# PERIPHERALS.net
KiCad netlist of a schematic drawn in Altium Designer
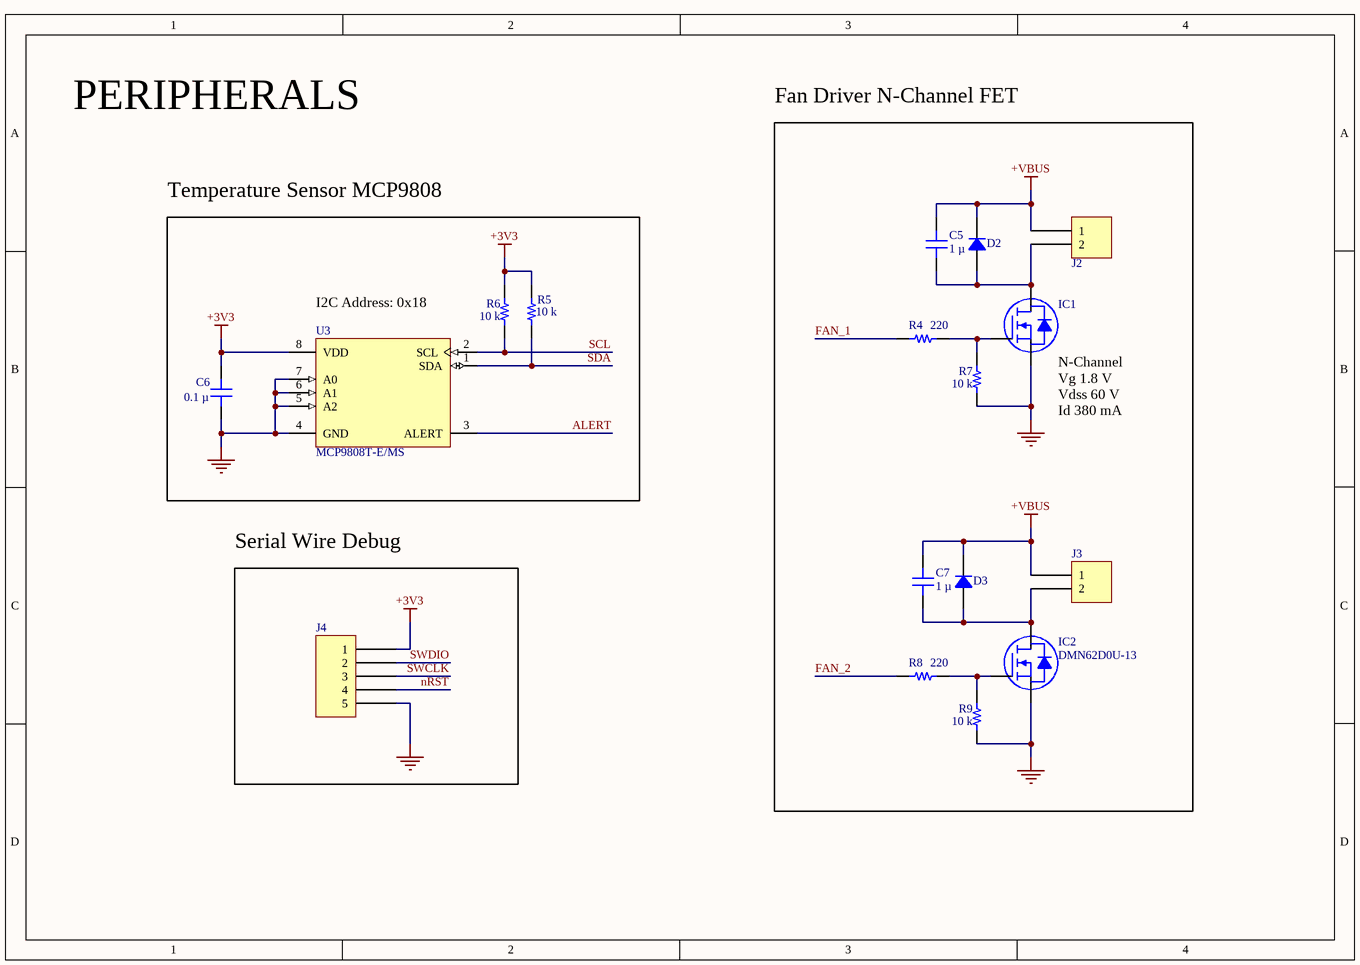
[diagram p0: PERIPHERALS.SchDoc]

(export (version "E")
  (design (tool "Eeschema 10.0.6"))
  (components
    (comp (ref "C5")
      (value "1 µ")
      (footprint "CAP 0603_1608")
      (description "CAP CER 1UF 16V X7R 0603")
      (fields (field (name "PART NUMBER") "C0603C105K4RACAUTO") (field (name "MANUFACTURER") "KEMET"))
      (libsource (lib "Celestial Altium Library - altium_library") (part "Capacitor"))
    )
    (comp (ref "C6")
      (value "0.1 µ")
      (footprint "CAP 0603_1608")
      (description "CAP CER 0.1UF 50V X7R 0603")
      (fields (field (name "PART NUMBER") "C0603C104K5RAC7411") (field (name "MANUFACTURER") "KEMET"))
      (libsource (lib "Celestial Altium Library - altium_library") (part "Capacitor"))
    )
    (comp (ref "C7")
      (value "1 µ")
      (footprint "CAP 0603_1608")
      (description "CAP CER 1UF 16V X7R 0603")
      (fields (field (name "PART NUMBER") "C0603C105K4RACAUTO") (field (name "MANUFACTURER") "KEMET"))
      (libsource (lib "Celestial Altium Library - altium_library") (part "Capacitor"))
    )
    (comp (ref "D2")
      (value "US1DWF-7")
      (footprint "SOD123F")
      (description "DIODE GEN PURP 200V 1A SOD123F")
      (fields (field (name "MANUFACTURER") "Diodes Incorporated"))
      (libsource (lib "Celestial Altium Library - altium_library") (part "Diode"))
    )
    (comp (ref "D3")
      (value "US1DWF-7")
      (footprint "SOD123F")
      (description "DIODE GEN PURP 200V 1A SOD123F")
      (fields (field (name "MANUFACTURER") "Diodes Incorporated"))
      (libsource (lib "Celestial Altium Library - altium_library") (part "Diode"))
    )
    (comp (ref "IC1")
      (value "DMN62D0U-13")
      (footprint "DIODES SOT-23-3")
      (description "MOSFET N-CH 60V 380MA SOT23")
      (fields (field (name "MANUFACTURER") "Diodes Incorporated"))
      (libsource (lib "Celestial Altium Library - altium_library") (part "DIODES INC MOSFET N-CH SOT-23-3"))
    )
    (comp (ref "IC2")
      (value "DMN62D0U-13")
      (footprint "DIODES SOT-23-3")
      (description "MOSFET N-CH 60V 380MA SOT23")
      (fields (field (name "MANUFACTURER") "Diodes Incorporated"))
      (libsource (lib "Celestial Altium Library - altium_library") (part "DIODES INC MOSFET N-CH SOT-23-3"))
    )
    (comp (ref "J2")
      (value "S2B-PH-SM4-TB(LF)(SN)")
      (footprint "JST S2B-PH-SM4-TB")
      (description "CONN HEADER SMD R/A 2POS 2MM")
      (fields (field (name "MANUFACTURER") "JST Sales America Inc."))
      (libsource (lib "Celestial Altium Library - altium_library") (part "2 Pin"))
    )
    (comp (ref "J3")
      (value "S2B-PH-SM4-TB(LF)(SN)")
      (footprint "JST S2B-PH-SM4-TB")
      (description "CONN HEADER SMD R/A 2POS 2MM")
      (fields (field (name "MANUFACTURER") "JST Sales America Inc."))
      (libsource (lib "Celestial Altium Library - altium_library") (part "2 Pin"))
    )
    (comp (ref "J4")
      (value "NPPN051BFCN-RC")
      (footprint "SULLINS NPPN051BFCN")
      (description "CONN HDR 5POS 0.079 GOLD PCB")
      (fields (field (name "MANUFACTURER") "Sullins Connector Solutions"))
      (libsource (lib "Celestial Altium Library - altium_library") (part "5 Pin"))
    )
    (comp (ref "R4")
      (value "220")
      (footprint "RES 0603_1608")
      (description "RES SMD 220 OHM 0.5% 1/10W 0603")
      (fields
        (field (name "PART NUMBER") "ERA-3AED221V")
        (field (name "MANUFACTURER") "Panasonic Electronic Components")
      )
      (libsource (lib "Celestial Altium Library - altium_library") (part "Resistor"))
    )
    (comp (ref "R5")
      (value "10 k")
      (footprint "RES 0603_1608")
      (description "RES 10K OHM 0.1% 1/16W 0603")
      (fields
        (field (name "PART NUMBER") "RNCS0603BKE10K0")
        (field (name "MANUFACTURER") "Stackpole Electronics Inc")
      )
      (libsource (lib "Celestial Altium Library - altium_library") (part "Resistor"))
    )
    (comp (ref "R6")
      (value "10 k")
      (footprint "RES 0603_1608")
      (description "RES 10K OHM 0.1% 1/16W 0603")
      (fields
        (field (name "PART NUMBER") "RNCS0603BKE10K0")
        (field (name "MANUFACTURER") "Stackpole Electronics Inc")
      )
      (libsource (lib "Celestial Altium Library - altium_library") (part "Resistor"))
    )
    (comp (ref "R7")
      (value "10 k")
      (footprint "RES 0603_1608")
      (description "RES 10K OHM 0.1% 1/16W 0603")
      (fields
        (field (name "PART NUMBER") "RNCS0603BKE10K0")
        (field (name "MANUFACTURER") "Stackpole Electronics Inc")
      )
      (libsource (lib "Celestial Altium Library - altium_library") (part "Resistor"))
    )
    (comp (ref "R8")
      (value "220")
      (footprint "RES 0603_1608")
      (description "RES SMD 220 OHM 0.5% 1/10W 0603")
      (fields
        (field (name "PART NUMBER") "ERA-3AED221V")
        (field (name "MANUFACTURER") "Panasonic Electronic Components")
      )
      (libsource (lib "Celestial Altium Library - altium_library") (part "Resistor"))
    )
    (comp (ref "R9")
      (value "10 k")
      (footprint "RES 0603_1608")
      (description "RES 10K OHM 0.1% 1/16W 0603")
      (fields
        (field (name "PART NUMBER") "RNCS0603BKE10K0")
        (field (name "MANUFACTURER") "Stackpole Electronics Inc")
      )
      (libsource (lib "Celestial Altium Library - altium_library") (part "Resistor"))
    )
    (comp (ref "U3")
      (value "MCP9808T-E/MS")
      (footprint "FP-C04-111-MFG")
      (description "Serial Switch/Digital Sensor, 16 Bit(s), 1Cel, Square, Surface Mount")
      (libsource (lib "University of South Florida") (part "MCP9808T-E/MS"))
    )
  )
  (nets
    (net (code "1") (name "+3V3") (class "Default")
      (node (ref "C6") (pin "2") (pinfunction "2_2") (pintype "passive"))
      (node (ref "J4") (pin "1") (pinfunction "1_1") (pintype "passive"))
      (node (ref "R5") (pin "2") (pinfunction "2_2") (pintype "passive"))
      (node (ref "R6") (pin "2") (pinfunction "2_2") (pintype "passive"))
      (node (ref "U3") (pin "8") (pinfunction "VDD_8") (pintype "power_in"))
    )
    (net (code "2") (name "+VBUS") (class "Default")
      (node (ref "C5") (pin "2") (pinfunction "2_2") (pintype "passive"))
      (node (ref "C7") (pin "2") (pinfunction "2_2") (pintype "passive"))
      (node (ref "D2") (pin "2") (pinfunction "2_2") (pintype "passive"))
      (node (ref "D3") (pin "2") (pinfunction "2_2") (pintype "passive"))
      (node (ref "J2") (pin "1") (pinfunction "1_1") (pintype "passive"))
      (node (ref "J3") (pin "1") (pinfunction "1_1") (pintype "passive"))
    )
    (net (code "4") (name "/ALERT") (class "Default")
      (node (ref "U3") (pin "3") (pinfunction "ALERT_3") (pintype "open_collector"))
    )
    (net (code "5") (name "/FAN_1") (class "Default")
      (node (ref "R4") (pin "1") (pinfunction "1_1") (pintype "passive"))
    )
    (net (code "6") (name "/FAN_2") (class "Default")
      (node (ref "R8") (pin "1") (pinfunction "1_1") (pintype "passive"))
    )
    (net (code "7") (name "/SCL") (class "Default")
      (node (ref "R6") (pin "1") (pinfunction "1_1") (pintype "passive"))
      (node (ref "U3") (pin "2") (pinfunction "SCL_2") (pintype "input"))
    )
    (net (code "8") (name "/SDA") (class "Default")
      (node (ref "R5") (pin "1") (pinfunction "1_1") (pintype "passive"))
      (node (ref "U3") (pin "1") (pinfunction "SDA_1") (pintype "bidirectional"))
    )
    (net (code "9") (name "/SWCLK") (class "Default")
      (node (ref "J4") (pin "3") (pinfunction "3_3") (pintype "passive"))
    )
    (net (code "10") (name "/SWDIO") (class "Default")
      (node (ref "J4") (pin "2") (pinfunction "2_2") (pintype "passive"))
    )
    (net (code "11") (name "/nRST") (class "Default")
      (node (ref "J4") (pin "4") (pinfunction "4_4") (pintype "passive"))
    )
    (net (code "12") (name "GND") (class "Default")
      (node (ref "C6") (pin "1") (pinfunction "1_1") (pintype "passive"))
      (node (ref "IC1") (pin "2") (pinfunction "S_2") (pintype "passive"))
      (node (ref "IC2") (pin "2") (pinfunction "S_2") (pintype "passive"))
      (node (ref "J4") (pin "5") (pinfunction "5_5") (pintype "passive"))
      (node (ref "R7") (pin "1") (pinfunction "1_1") (pintype "passive"))
      (node (ref "R9") (pin "1") (pinfunction "1_1") (pintype "passive"))
      (node (ref "U3") (pin "4") (pinfunction "GND_4") (pintype "power_in"))
      (node (ref "U3") (pin "5") (pinfunction "A2_5") (pintype "input"))
      (node (ref "U3") (pin "6") (pinfunction "A1_6") (pintype "input"))
      (node (ref "U3") (pin "7") (pinfunction "A0_7") (pintype "input"))
    )
    (net (code "13") (name "Net-(IC1-D)") (class "Default")
      (node (ref "C5") (pin "1") (pinfunction "1_1") (pintype "passive"))
      (node (ref "D2") (pin "1") (pinfunction "1_1") (pintype "passive"))
      (node (ref "IC1") (pin "3") (pinfunction "D_3") (pintype "passive"))
      (node (ref "J2") (pin "2") (pinfunction "2_2") (pintype "passive"))
    )
    (net (code "14") (name "Net-(IC1-G)") (class "Default")
      (node (ref "IC1") (pin "1") (pinfunction "G_1") (pintype "passive"))
      (node (ref "R4") (pin "2") (pinfunction "2_2") (pintype "passive"))
      (node (ref "R7") (pin "2") (pinfunction "2_2") (pintype "passive"))
    )
    (net (code "15") (name "Net-(IC2-D)") (class "Default")
      (node (ref "C7") (pin "1") (pinfunction "1_1") (pintype "passive"))
      (node (ref "D3") (pin "1") (pinfunction "1_1") (pintype "passive"))
      (node (ref "IC2") (pin "3") (pinfunction "D_3") (pintype "passive"))
      (node (ref "J3") (pin "2") (pinfunction "2_2") (pintype "passive"))
    )
    (net (code "16") (name "Net-(IC2-G)") (class "Default")
      (node (ref "IC2") (pin "1") (pinfunction "G_1") (pintype "passive"))
      (node (ref "R8") (pin "2") (pinfunction "2_2") (pintype "passive"))
      (node (ref "R9") (pin "2") (pinfunction "2_2") (pintype "passive"))
    )
  )
)
